# ESP32_Microphone.net
KiCad netlist of a schematic drawn in Altium Designer
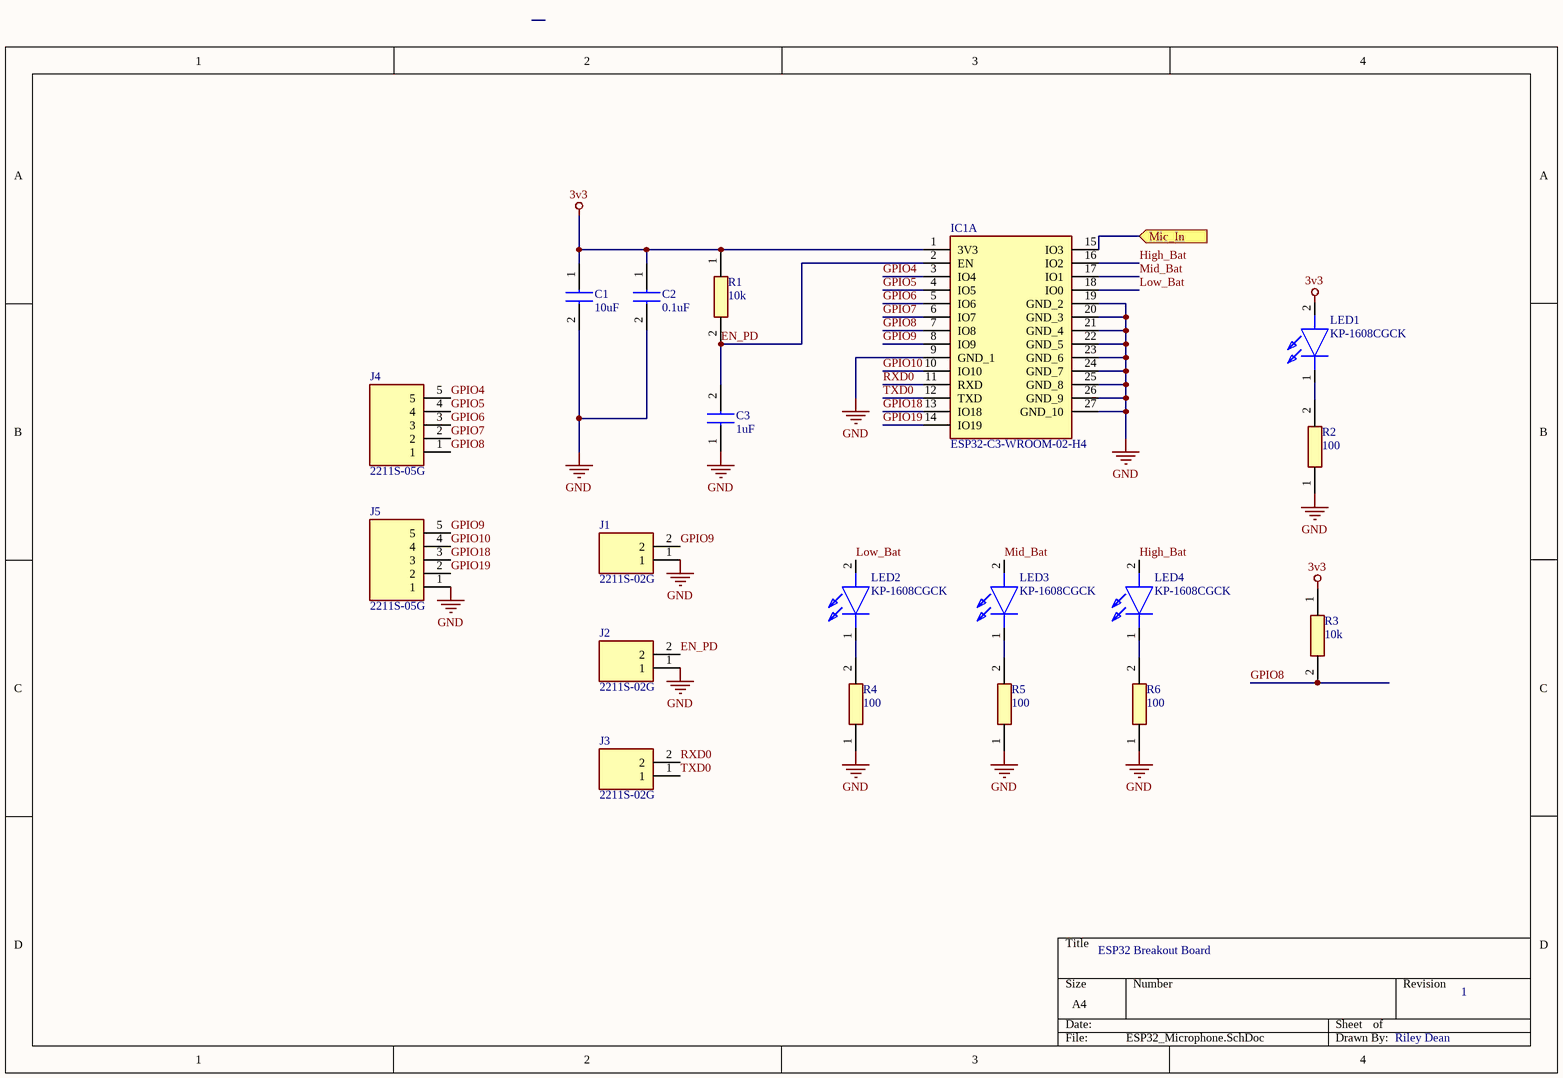
[diagram p0: ESP32_Microphone.SchDoc]

(export (version "E")
  (design (tool "Eeschema 10.0.6"))
  (components
    (comp (ref "C1")
      (value "10uF")
      (footprint "SamacSys:C0805")
      (description "Capacitor")
      (fields
        (field (name "MANUFACTURER_PART_NUMBER") "C0805C106K4PACTU")
        (field (name "MOUSER PART NUMBER") "80-C0805C106K4P")
      )
      (libsource (lib "*") (part "C0805C106K4PACTU"))
    )
    (comp (ref "C2")
      (value "0.1uF")
      (footprint "SamacSys:CAPC1608X90N")
      (description "Capacitor")
      (fields
        (field (name "MANUFACTURER_PART_NUMBER") "CC0603KRX7R7BB104")
        (field (name "MOUSER PART NUMBER") "603-CC603KRX7R7BB104")
      )
      (libsource (lib "SamacSys") (part "CC0603KRX7R7BB104"))
    )
    (comp (ref "C3")
      (value "1uF")
      (footprint "SamacSys:CAPC1608X90N")
      (description "Capacitor")
      (fields (field (name "MANUFACTURER_PART_NUMBER") "C0603C105K4RACTU7042"))
      (libsource (lib "*") (part "C0603C105K4RACTU7042"))
    )
    (comp (ref "IC1")
      (value "ESP32-C3-WROOM-02-H4")
      (footprint "SamacSys:ESP32C3WROOM02H4")
      (description "Integrated Circuit")
      (fields (field (name "MOUSER PART NUMBER") "356-ESP32C3WROOM02H4"))
      (libsource (lib "SamacSys") (part "ESP32-C3-WROOM-02-H4"))
    )
    (comp (ref "J1")
      (value "2211S-02G")
      (footprint "SamacSys:HDRV2W64P0X254_1X2_508X254X874P")
      (description "Connector")
      (libsource (lib "*") (part "2211S-02G"))
    )
    (comp (ref "J2")
      (value "2211S-02G")
      (footprint "SamacSys:HDRV2W64P0X254_1X2_508X254X874P")
      (description "Connector")
      (libsource (lib "*") (part "2211S-02G"))
    )
    (comp (ref "J3")
      (value "2211S-02G")
      (footprint "SamacSys:HDRV2W64P0X254_1X2_508X254X874P")
      (description "Connector")
      (libsource (lib "*") (part "2211S-02G"))
    )
    (comp (ref "J4")
      (value "2211S-05G")
      (footprint "SamacSys:HDRV5W90P0X254_1X5_1270X254X1174P")
      (description "Connector")
      (libsource (lib "*") (part "2211S-05G"))
    )
    (comp (ref "J5")
      (value "2211S-05G")
      (footprint "SamacSys:HDRV5W90P0X254_1X5_1270X254X1174P")
      (description "Connector")
      (libsource (lib "*") (part "2211S-05G"))
    )
    (comp (ref "LED1")
      (value "KP-1608CGCK")
      (footprint "SamacSys:LEDC1608X120N")
      (description "LED")
      (libsource (lib "*") (part "KP-1608CGCK"))
    )
    (comp (ref "LED2")
      (value "KP-1608CGCK")
      (footprint "SamacSys:LEDC1608X120N")
      (description "LED")
      (libsource (lib "*") (part "KP-1608CGCK"))
    )
    (comp (ref "LED3")
      (value "KP-1608CGCK")
      (footprint "SamacSys:LEDC1608X120N")
      (description "LED")
      (libsource (lib "*") (part "KP-1608CGCK"))
    )
    (comp (ref "LED4")
      (value "KP-1608CGCK")
      (footprint "SamacSys:LEDC1608X120N")
      (description "LED")
      (libsource (lib "*") (part "KP-1608CGCK"))
    )
    (comp (ref "R1")
      (value "10k")
      (footprint "SamacSys:RESC1608X55N")
      (description "Resistor")
      (fields
        (field (name "MANUFACTURER_PART_NUMBER") "RC0603FR-0710KL")
        (field (name "MOUSER PART NUMBER") "603-RC0603FR-0710KL")
      )
      (libsource (lib "SamacSys") (part "RC0603FR-0710KL"))
    )
    (comp (ref "R2")
      (value "100")
      (footprint "SamacSys:RESC1608X55N")
      (description "Resistor")
      (fields (field (name "MANUFACTURER_PART_NUMBER") "RC0603JR07470RL"))
      (libsource (lib "*") (part "RC0603JR07470RL"))
    )
    (comp (ref "R3")
      (value "10k")
      (footprint "SamacSys:RESC1608X55N")
      (description "Resistor")
      (fields
        (field (name "MANUFACTURER_PART_NUMBER") "RC0603FR-0710KL")
        (field (name "MOUSER PART NUMBER") "603-RC0603FR-0710KL")
      )
      (libsource (lib "SamacSys") (part "RC0603FR-0710KL"))
    )
    (comp (ref "R4")
      (value "100")
      (footprint "SamacSys:RESC1608X55N")
      (description "Resistor")
      (fields (field (name "MANUFACTURER_PART_NUMBER") "RC0603JR07470RL"))
      (libsource (lib "*") (part "RC0603JR07470RL"))
    )
    (comp (ref "R5")
      (value "100")
      (footprint "SamacSys:RESC1608X55N")
      (description "Resistor")
      (fields (field (name "MANUFACTURER_PART_NUMBER") "RC0603JR07470RL"))
      (libsource (lib "*") (part "RC0603JR07470RL"))
    )
    (comp (ref "R6")
      (value "100")
      (footprint "SamacSys:RESC1608X55N")
      (description "Resistor")
      (fields (field (name "MANUFACTURER_PART_NUMBER") "RC0603JR07470RL"))
      (libsource (lib "*") (part "RC0603JR07470RL"))
    )
  )
  (nets
    (net (code "1") (name "/EN_PD") (class "Default")
      (node (ref "C3") (pin "2") (pinfunction "2_2") (pintype "passive"))
      (node (ref "IC1") (pin "2") (pinfunction "EN_2") (pintype "passive"))
      (node (ref "J2") (pin "2") (pinfunction "2_2") (pintype "passive"))
      (node (ref "R1") (pin "2") (pinfunction "2_2") (pintype "passive"))
    )
    (net (code "2") (name "/GPIO4") (class "Default")
      (node (ref "IC1") (pin "3") (pinfunction "IO4_3") (pintype "passive"))
      (node (ref "J4") (pin "5") (pinfunction "5_5") (pintype "passive"))
    )
    (net (code "3") (name "/GPIO5") (class "Default")
      (node (ref "IC1") (pin "4") (pinfunction "IO5_4") (pintype "passive"))
      (node (ref "J4") (pin "4") (pinfunction "4_4") (pintype "passive"))
    )
    (net (code "4") (name "/GPIO6") (class "Default")
      (node (ref "IC1") (pin "5") (pinfunction "IO6_5") (pintype "passive"))
      (node (ref "J4") (pin "3") (pinfunction "3_3") (pintype "passive"))
    )
    (net (code "5") (name "/GPIO7") (class "Default")
      (node (ref "IC1") (pin "6") (pinfunction "IO7_6") (pintype "passive"))
      (node (ref "J4") (pin "2") (pinfunction "2_2") (pintype "passive"))
    )
    (net (code "6") (name "/GPIO8") (class "Default")
      (node (ref "IC1") (pin "7") (pinfunction "IO8_7") (pintype "passive"))
      (node (ref "J4") (pin "1") (pinfunction "1_1") (pintype "passive"))
      (node (ref "R3") (pin "2") (pinfunction "2_2") (pintype "passive"))
    )
    (net (code "7") (name "/GPIO9") (class "Default")
      (node (ref "IC1") (pin "8") (pinfunction "IO9_8") (pintype "passive"))
      (node (ref "J1") (pin "2") (pinfunction "2_2") (pintype "passive"))
      (node (ref "J5") (pin "5") (pinfunction "5_5") (pintype "passive"))
    )
    (net (code "8") (name "/GPIO10") (class "Default")
      (node (ref "IC1") (pin "10") (pinfunction "IO10_10") (pintype "passive"))
      (node (ref "J5") (pin "4") (pinfunction "4_4") (pintype "passive"))
    )
    (net (code "9") (name "/GPIO18") (class "Default")
      (node (ref "IC1") (pin "13") (pinfunction "IO18_13") (pintype "passive"))
      (node (ref "J5") (pin "3") (pinfunction "3_3") (pintype "passive"))
    )
    (net (code "10") (name "/GPIO19") (class "Default")
      (node (ref "IC1") (pin "14") (pinfunction "IO19_14") (pintype "passive"))
      (node (ref "J5") (pin "2") (pinfunction "2_2") (pintype "passive"))
    )
    (net (code "11") (name "/High_Bat") (class "Default")
      (node (ref "IC1") (pin "16") (pinfunction "IO2_16") (pintype "passive"))
      (node (ref "LED4") (pin "2") (pinfunction "A_2") (pintype "passive"))
    )
    (net (code "12") (name "/Low_Bat") (class "Default")
      (node (ref "IC1") (pin "18") (pinfunction "IO0_18") (pintype "passive"))
      (node (ref "LED2") (pin "2") (pinfunction "A_2") (pintype "passive"))
    )
    (net (code "13") (name "/Mic_In") (class "Default")
      (node (ref "IC1") (pin "15") (pinfunction "IO3_15") (pintype "passive"))
    )
    (net (code "14") (name "/Mid_Bat") (class "Default")
      (node (ref "IC1") (pin "17") (pinfunction "IO1_17") (pintype "passive"))
      (node (ref "LED3") (pin "2") (pinfunction "A_2") (pintype "passive"))
    )
    (net (code "15") (name "/RXD0") (class "Default")
      (node (ref "IC1") (pin "11") (pinfunction "RXD_11") (pintype "passive"))
      (node (ref "J3") (pin "2") (pinfunction "2_2") (pintype "passive"))
    )
    (net (code "16") (name "/TXD0") (class "Default")
      (node (ref "IC1") (pin "12") (pinfunction "TXD_12") (pintype "passive"))
      (node (ref "J3") (pin "1") (pinfunction "1_1") (pintype "passive"))
    )
    (net (code "17") (name "3v3") (class "Default")
      (node (ref "C1") (pin "1") (pinfunction "1_1") (pintype "passive"))
      (node (ref "C2") (pin "1") (pinfunction "1_1") (pintype "passive"))
      (node (ref "IC1") (pin "1") (pinfunction "3V3_1") (pintype "passive"))
      (node (ref "LED1") (pin "2") (pinfunction "A_2") (pintype "passive"))
      (node (ref "R1") (pin "1") (pinfunction "1_1") (pintype "passive"))
      (node (ref "R3") (pin "1") (pinfunction "1_1") (pintype "passive"))
    )
    (net (code "18") (name "GND") (class "Default")
      (node (ref "C1") (pin "2") (pinfunction "2_2") (pintype "passive"))
      (node (ref "C2") (pin "2") (pinfunction "2_2") (pintype "passive"))
      (node (ref "C3") (pin "1") (pinfunction "1_1") (pintype "passive"))
      (node (ref "IC1") (pin "19") (pinfunction "GND_2_19") (pintype "passive"))
      (node (ref "IC1") (pin "20") (pinfunction "GND_3_20") (pintype "passive"))
      (node (ref "IC1") (pin "21") (pinfunction "GND_4_21") (pintype "passive"))
      (node (ref "IC1") (pin "22") (pinfunction "GND_5_22") (pintype "passive"))
      (node (ref "IC1") (pin "23") (pinfunction "GND_6_23") (pintype "passive"))
      (node (ref "IC1") (pin "24") (pinfunction "GND_7_24") (pintype "passive"))
      (node (ref "IC1") (pin "25") (pinfunction "GND_8_25") (pintype "passive"))
      (node (ref "IC1") (pin "26") (pinfunction "GND_9_26") (pintype "passive"))
      (node (ref "IC1") (pin "27") (pinfunction "GND_10_27") (pintype "passive"))
      (node (ref "IC1") (pin "9") (pinfunction "GND_1_9") (pintype "passive"))
      (node (ref "J1") (pin "1") (pinfunction "1_1") (pintype "passive"))
      (node (ref "J2") (pin "1") (pinfunction "1_1") (pintype "passive"))
      (node (ref "J5") (pin "1") (pinfunction "1_1") (pintype "passive"))
      (node (ref "R2") (pin "1") (pinfunction "1_1") (pintype "passive"))
      (node (ref "R4") (pin "1") (pinfunction "1_1") (pintype "passive"))
      (node (ref "R5") (pin "1") (pinfunction "1_1") (pintype "passive"))
      (node (ref "R6") (pin "1") (pinfunction "1_1") (pintype "passive"))
    )
    (net (code "19") (name "Net-(LED1-K)") (class "Default")
      (node (ref "LED1") (pin "1") (pinfunction "K_1") (pintype "passive"))
      (node (ref "R2") (pin "2") (pinfunction "2_2") (pintype "passive"))
    )
    (net (code "20") (name "Net-(LED2-K)") (class "Default")
      (node (ref "LED2") (pin "1") (pinfunction "K_1") (pintype "passive"))
      (node (ref "R4") (pin "2") (pinfunction "2_2") (pintype "passive"))
    )
    (net (code "21") (name "Net-(LED3-K)") (class "Default")
      (node (ref "LED3") (pin "1") (pinfunction "K_1") (pintype "passive"))
      (node (ref "R5") (pin "2") (pinfunction "2_2") (pintype "passive"))
    )
    (net (code "22") (name "Net-(LED4-K)") (class "Default")
      (node (ref "LED4") (pin "1") (pinfunction "K_1") (pintype "passive"))
      (node (ref "R6") (pin "2") (pinfunction "2_2") (pintype "passive"))
    )
  )
)
